# AccelCircuit_Schematic.net
KiCad netlist of a schematic drawn in EasyEDA
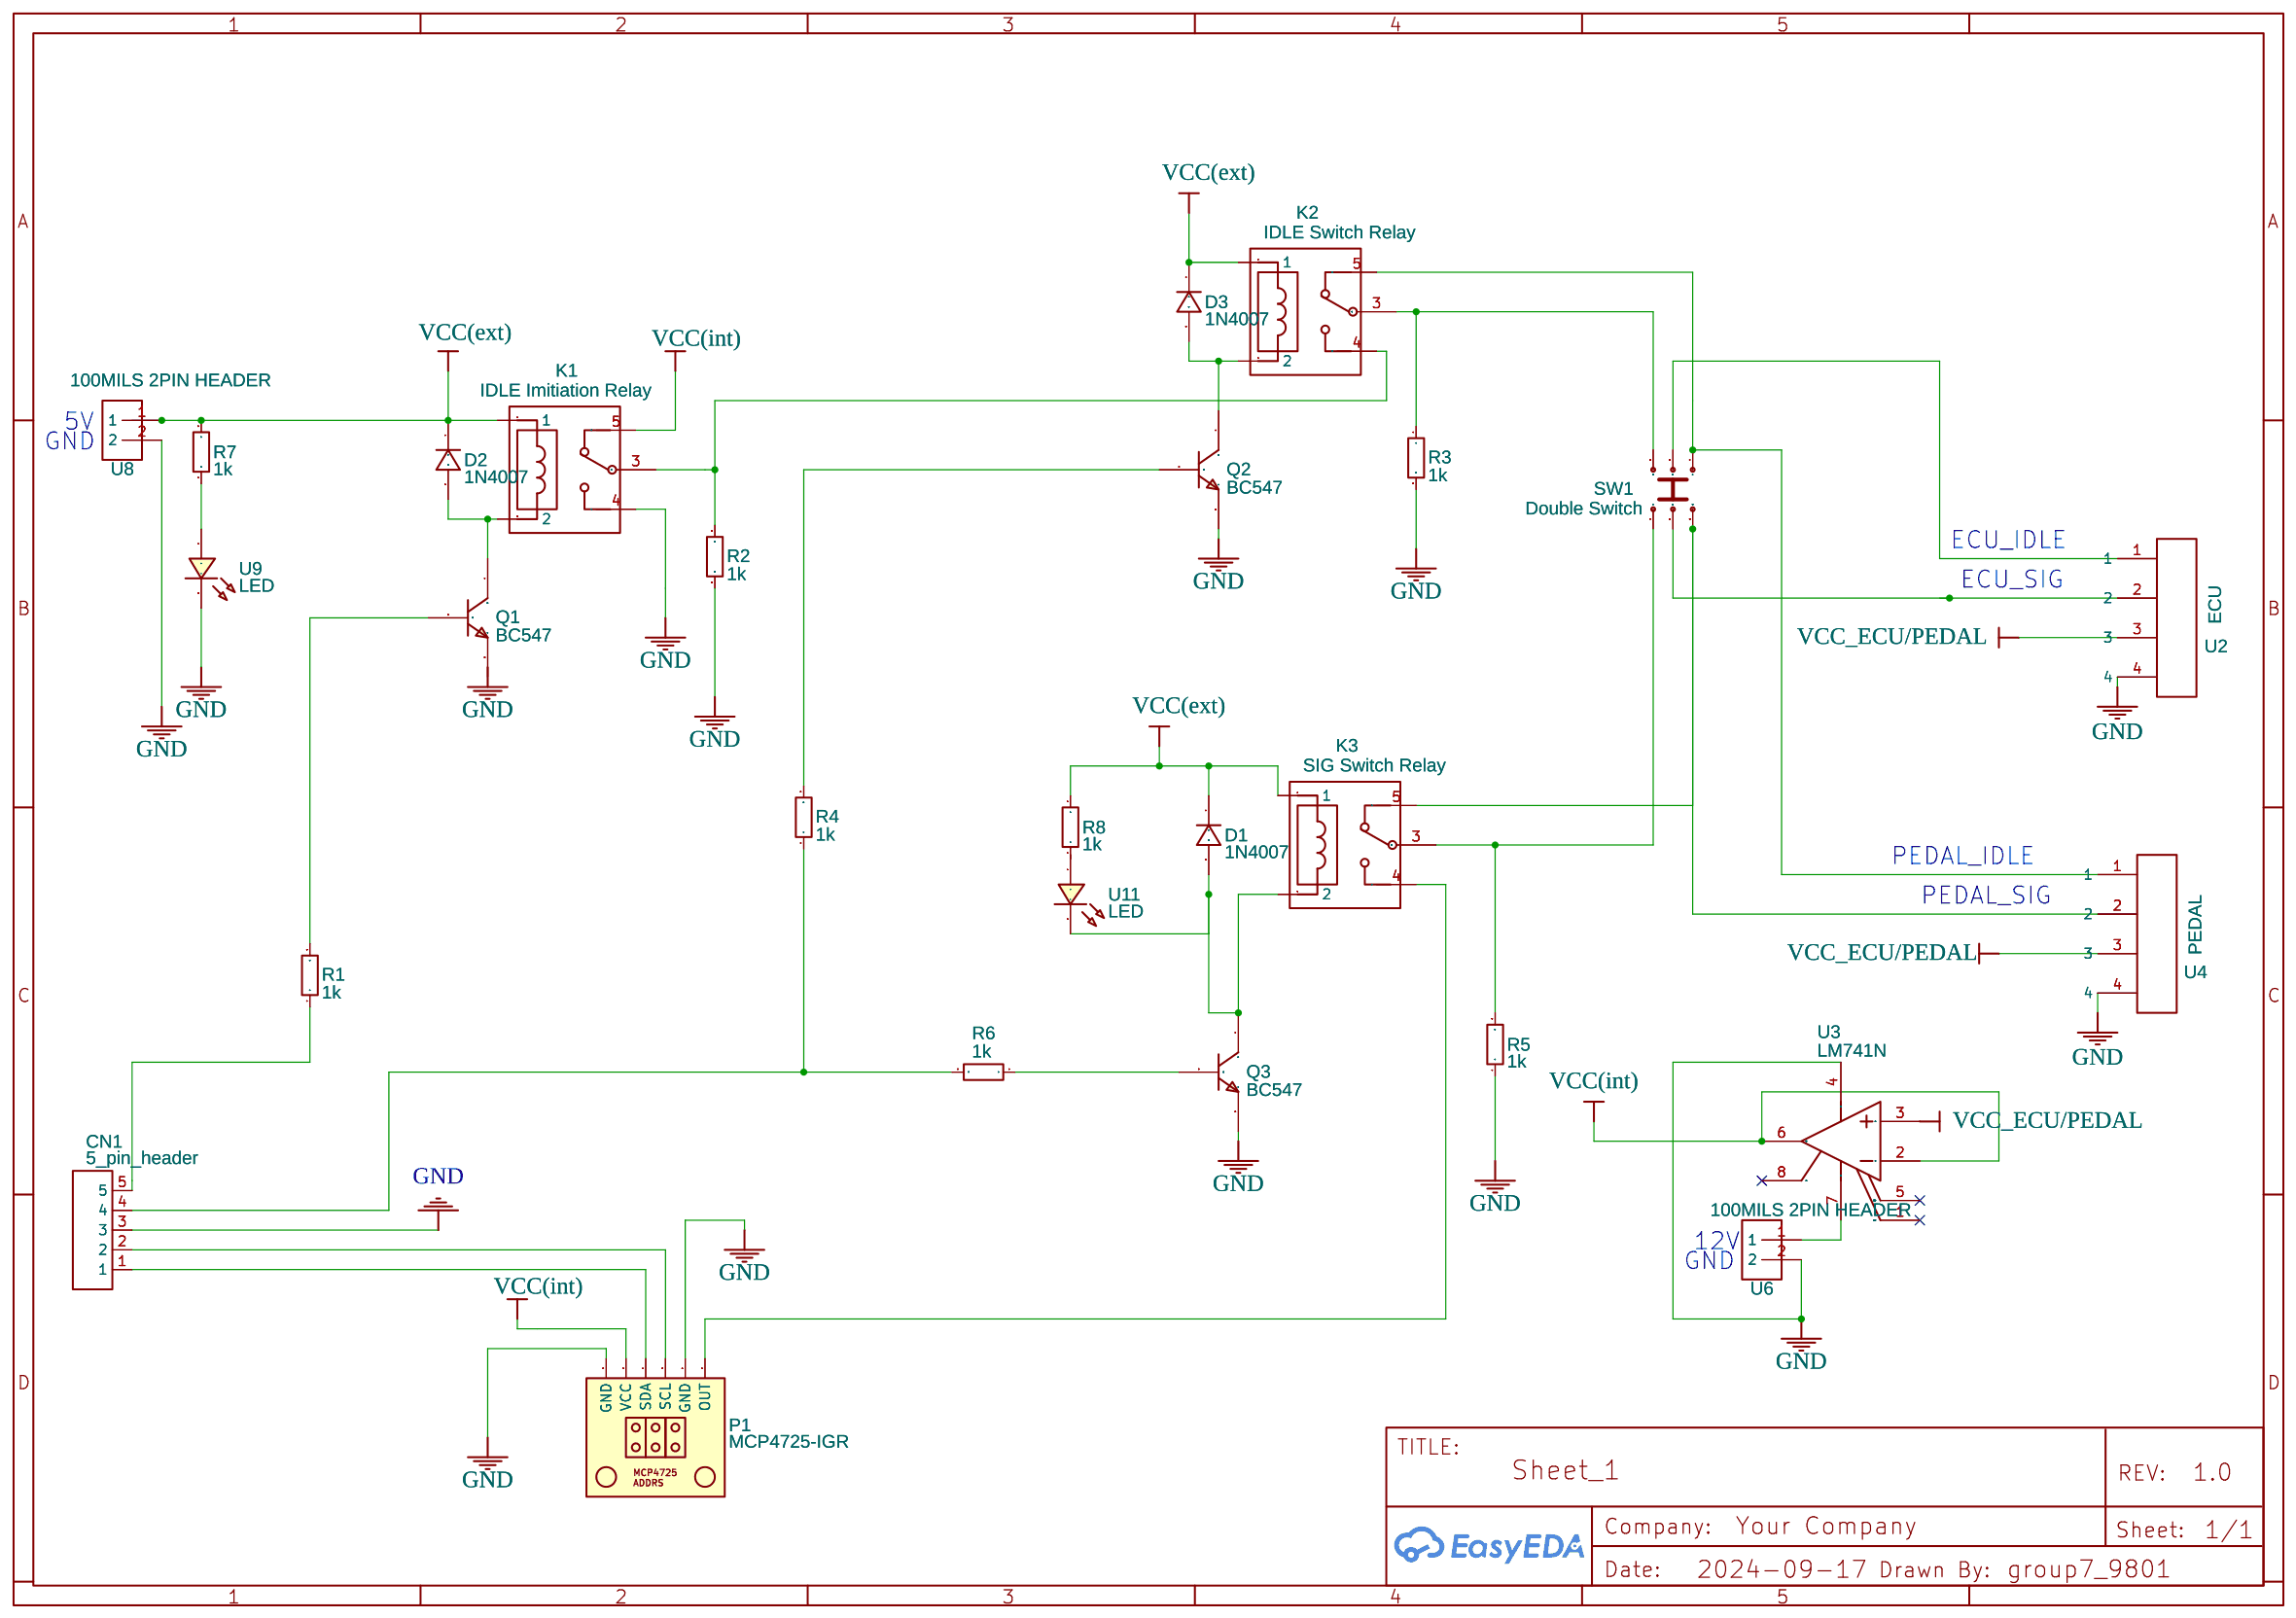
[diagram p0: schematic sheet]

(export (version "E")
  (design (tool "Eeschema 10.0.6"))
  (components
    (comp (ref "CN1")
      (value "5_pin_header")
      (fields (field (name "Manufacturer Part") "559320510") (field (name "Manufacturer") "MOLEX"))
      (libsource (lib "") (part "5_pin_header"))
    )
    (comp (ref "D1")
      (value "1N4007")
      (fields (field (name "Manufacturer") "SEMTECH"))
      (libsource (lib "") (part "1N4007"))
    )
    (comp (ref "D2")
      (value "1N4007")
      (fields (field (name "Manufacturer") "SEMTECH"))
      (libsource (lib "") (part "1N4007"))
    )
    (comp (ref "D3")
      (value "1N4007")
      (fields (field (name "Manufacturer") "SEMTECH"))
      (libsource (lib "") (part "1N4007"))
    )
    (comp (ref "K1") (value "IDLE Imitiation Relay") (libsource (lib "") (part "HRS4H-S-5V RELAY")))
    (comp (ref "K2") (value "IDLE Switch Relay") (libsource (lib "") (part "HRS4H-S-5V RELAY")))
    (comp (ref "K3") (value "SIG Switch Relay") (libsource (lib "") (part "HRS4H-S-5V RELAY")))
    (comp (ref "P1") (value "MCP4725-IGR") (libsource (lib "") (part "MCP4725-IGR")))
    (comp (ref "Q1") (value "BC547") (libsource (lib "") (part "BC547")))
    (comp (ref "Q2") (value "BC547") (libsource (lib "") (part "BC547")))
    (comp (ref "Q3") (value "BC547") (libsource (lib "") (part "BC547")))
    (comp (ref "R1")
      (value "1k")
      (fields
        (field (name "Manufacturer Part") "EWWR0001J20R0T9")
        (field (name "Manufacturer") "ResistorToday")
      )
      (libsource (lib "") (part "RESISTOR NORMAL"))
    )
    (comp (ref "R2")
      (value "1k")
      (fields
        (field (name "Manufacturer Part") "EWWR0001J20R0T9")
        (field (name "Manufacturer") "ResistorToday")
      )
      (libsource (lib "") (part "RESISTOR NORMAL_1"))
    )
    (comp (ref "R3")
      (value "1k")
      (fields
        (field (name "Manufacturer Part") "EWWR0001J20R0T9")
        (field (name "Manufacturer") "ResistorToday")
      )
      (libsource (lib "") (part "RESISTOR NORMAL_1"))
    )
    (comp (ref "R4")
      (value "1k")
      (fields
        (field (name "Manufacturer Part") "EWWR0001J20R0T9")
        (field (name "Manufacturer") "ResistorToday")
      )
      (libsource (lib "") (part "RESISTOR NORMAL"))
    )
    (comp (ref "R5")
      (value "1k")
      (fields
        (field (name "Manufacturer Part") "EWWR0001J20R0T9")
        (field (name "Manufacturer") "ResistorToday")
      )
      (libsource (lib "") (part "RESISTOR NORMAL"))
    )
    (comp (ref "R6")
      (value "1k")
      (fields
        (field (name "Manufacturer Part") "EWWR0001J20R0T9")
        (field (name "Manufacturer") "ResistorToday")
      )
      (libsource (lib "") (part "RESISTOR NORMAL_2"))
    )
    (comp (ref "R7")
      (value "1k")
      (fields
        (field (name "Manufacturer Part") "EWWR0001J20R0T9")
        (field (name "Manufacturer") "ResistorToday")
      )
      (libsource (lib "") (part "RESISTOR NORMAL"))
    )
    (comp (ref "R8")
      (value "1k")
      (fields
        (field (name "Manufacturer Part") "EWWR0001J20R0T9")
        (field (name "Manufacturer") "ResistorToday")
      )
      (libsource (lib "") (part "RESISTOR NORMAL"))
    )
    (comp (ref "SW1")
      (value "Double Switch")
      (fields
        (field (name "Manufacturer Part") "SK-12D02-VG5")
        (field (name "Manufacturer") "Rectangular Connectors - Contacts")
      )
      (libsource (lib "") (part "Double_Switch_2Pos"))
    )
    (comp (ref "U2") (value "ECU") (libsource (lib "") (part "200mils_4Pin_Header")))
    (comp (ref "U3")
      (value "LM741N")
      (fields (field (name "Manufacturer") "HGSEMI(华冠)"))
      (libsource (lib "") (part "LM741N"))
    )
    (comp (ref "U4") (value "PEDAL") (libsource (lib "") (part "200mils_4Pin_Header")))
    (comp (ref "U6") (value "100MILS 2PIN HEADER") (libsource (lib "") (part "100MILS 2PIN HEADER")))
    (comp (ref "U8") (value "100MILS 2PIN HEADER") (libsource (lib "") (part "100MILS 2PIN HEADER")))
    (comp (ref "U9")
      (value "LED")
      (fields (field (name "Manufacturer Part") "32LED-RED") (field (name "Manufacturer") "Grayhill"))
      (libsource (lib "") (part "32LED-RED"))
    )
    (comp (ref "U11")
      (value "LED")
      (fields (field (name "Manufacturer Part") "32LED-RED") (field (name "Manufacturer") "Grayhill"))
      (libsource (lib "") (part "32LED-RED"))
    )
  )
  (nets
    (net (code "1") (name "GND") (class "Default")
      (node (ref "CN1") (pin "3") (pinfunction "3_3") (pintype "unspecified"))
      (node (ref "K1") (pin "4") (pinfunction "4_4") (pintype "unspecified"))
      (node (ref "P1") (pin "2") (pinfunction "GND_2") (pintype "unspecified"))
      (node (ref "P1") (pin "6") (pinfunction "GND_6") (pintype "unspecified"))
      (node (ref "Q1") (pin "3") (pinfunction "E_3") (pintype "unspecified"))
      (node (ref "Q2") (pin "3") (pinfunction "E_3") (pintype "unspecified"))
      (node (ref "Q3") (pin "3") (pinfunction "E_3") (pintype "unspecified"))
      (node (ref "R2") (pin "2") (pinfunction "2_2") (pintype "unspecified"))
      (node (ref "R3") (pin "2") (pinfunction "2_2") (pintype "unspecified"))
      (node (ref "R5") (pin "1") (pinfunction "1_1") (pintype "unspecified"))
      (node (ref "U2") (pin "4") (pinfunction "4_4") (pintype "unspecified"))
      (node (ref "U3") (pin "4") (pinfunction "V-_4") (pintype "passive"))
      (node (ref "U4") (pin "4") (pinfunction "4_4") (pintype "unspecified"))
      (node (ref "U6") (pin "2") (pinfunction "2_2") (pintype "unspecified"))
      (node (ref "U8") (pin "2") (pinfunction "2_2") (pintype "unspecified"))
      (node (ref "U9") (pin "2") (pinfunction "-_2") (pintype "unspecified"))
    )
    (net (code "2") (name "Net-(CN1-Pad4)") (class "Default")
      (node (ref "CN1") (pin "4") (pinfunction "4_4") (pintype "unspecified"))
      (node (ref "R4") (pin "1") (pinfunction "1_1") (pintype "unspecified"))
      (node (ref "R6") (pin "2") (pinfunction "2_2") (pintype "unspecified"))
    )
    (net (code "3") (name "Net-(CN1-Pad5)") (class "Default")
      (node (ref "CN1") (pin "5") (pinfunction "5_5") (pintype "unspecified"))
      (node (ref "R1") (pin "1") (pinfunction "1_1") (pintype "unspecified"))
    )
    (net (code "4") (name "Net-(K1-Pad3)") (class "Default")
      (node (ref "K1") (pin "3") (pinfunction "3_3") (pintype "unspecified"))
      (node (ref "K2") (pin "4") (pinfunction "4_4") (pintype "unspecified"))
      (node (ref "R2") (pin "1") (pinfunction "1_1") (pintype "unspecified"))
    )
    (net (code "5") (name "Net-(K2-Pad3)") (class "Default")
      (node (ref "K2") (pin "3") (pinfunction "3_3") (pintype "unspecified"))
      (node (ref "R3") (pin "1") (pinfunction "1_1") (pintype "unspecified"))
      (node (ref "SW1") (pin "3") (pinfunction "3_3") (pintype "unspecified"))
    )
    (net (code "6") (name "Net-(K2-Pad5)") (class "Default")
      (node (ref "K2") (pin "5") (pinfunction "5_5") (pintype "unspecified"))
      (node (ref "SW1") (pin "1") (pinfunction "1_1") (pintype "unspecified"))
      (node (ref "U4") (pin "1") (pinfunction "1_1") (pintype "unspecified"))
    )
    (net (code "7") (name "Net-(K3-Pad3)") (class "Default")
      (node (ref "K3") (pin "3") (pinfunction "3_3") (pintype "unspecified"))
      (node (ref "R5") (pin "2") (pinfunction "2_2") (pintype "unspecified"))
      (node (ref "SW1") (pin "4") (pinfunction "4_4") (pintype "unspecified"))
    )
    (net (code "8") (name "Net-(K3-Pad5)") (class "Default")
      (node (ref "K3") (pin "5") (pinfunction "5_5") (pintype "unspecified"))
      (node (ref "SW1") (pin "6") (pinfunction "6_6") (pintype "unspecified"))
      (node (ref "U4") (pin "2") (pinfunction "2_2") (pintype "unspecified"))
    )
    (net (code "9") (name "Net-(P1-OUT)") (class "Default")
      (node (ref "K3") (pin "4") (pinfunction "4_4") (pintype "unspecified"))
      (node (ref "P1") (pin "1") (pinfunction "OUT_1") (pintype "unspecified"))
    )
    (net (code "10") (name "Net-(P1-SCL)") (class "Default")
      (node (ref "CN1") (pin "2") (pinfunction "2_2") (pintype "unspecified"))
      (node (ref "P1") (pin "3") (pinfunction "SCL_3") (pintype "unspecified"))
    )
    (net (code "11") (name "Net-(P1-SDA)") (class "Default")
      (node (ref "CN1") (pin "1") (pinfunction "1_1") (pintype "unspecified"))
      (node (ref "P1") (pin "4") (pinfunction "SDA_4") (pintype "unspecified"))
    )
    (net (code "12") (name "Net-(Q1-B)") (class "Default")
      (node (ref "Q1") (pin "2") (pinfunction "B_2") (pintype "unspecified"))
      (node (ref "R1") (pin "2") (pinfunction "2_2") (pintype "unspecified"))
    )
    (net (code "13") (name "Net-(Q1-C)") (class "Default")
      (node (ref "D2") (pin "2") (pinfunction "2_2") (pintype "unspecified"))
      (node (ref "K1") (pin "2") (pinfunction "2_2") (pintype "unspecified"))
      (node (ref "Q1") (pin "1") (pinfunction "C_1") (pintype "unspecified"))
    )
    (net (code "14") (name "Net-(Q2-B)") (class "Default")
      (node (ref "Q2") (pin "2") (pinfunction "B_2") (pintype "unspecified"))
      (node (ref "R4") (pin "2") (pinfunction "2_2") (pintype "unspecified"))
    )
    (net (code "15") (name "Net-(Q2-C)") (class "Default")
      (node (ref "D3") (pin "2") (pinfunction "2_2") (pintype "unspecified"))
      (node (ref "K2") (pin "2") (pinfunction "2_2") (pintype "unspecified"))
      (node (ref "Q2") (pin "1") (pinfunction "C_1") (pintype "unspecified"))
    )
    (net (code "16") (name "Net-(Q3-B)") (class "Default")
      (node (ref "Q3") (pin "2") (pinfunction "B_2") (pintype "unspecified"))
      (node (ref "R6") (pin "1") (pinfunction "1_1") (pintype "unspecified"))
    )
    (net (code "17") (name "Net-(Q3-C)") (class "Default")
      (node (ref "D1") (pin "2") (pinfunction "2_2") (pintype "unspecified"))
      (node (ref "K3") (pin "2") (pinfunction "2_2") (pintype "unspecified"))
      (node (ref "Q3") (pin "1") (pinfunction "C_1") (pintype "unspecified"))
      (node (ref "U11") (pin "2") (pinfunction "-_2") (pintype "unspecified"))
    )
    (net (code "18") (name "Net-(SW1-Pad2)") (class "Default")
      (node (ref "SW1") (pin "2") (pinfunction "2_2") (pintype "unspecified"))
      (node (ref "U2") (pin "1") (pinfunction "1_1") (pintype "unspecified"))
    )
    (net (code "19") (name "Net-(SW1-Pad5)") (class "Default")
      (node (ref "SW1") (pin "5") (pinfunction "5_5") (pintype "unspecified"))
      (node (ref "U2") (pin "2") (pinfunction "2_2") (pintype "unspecified"))
    )
    (net (code "20") (name "Net-(U3-V+)") (class "Default")
      (node (ref "U3") (pin "7") (pinfunction "V+_7") (pintype "passive"))
      (node (ref "U6") (pin "1") (pinfunction "1_1") (pintype "unspecified"))
    )
    (net (code "21") (name "Net-(U9-+)") (class "Default")
      (node (ref "R7") (pin "1") (pinfunction "1_1") (pintype "unspecified"))
      (node (ref "U9") (pin "1") (pinfunction "+_1") (pintype "unspecified"))
    )
    (net (code "22") (name "Net-(U11-+)") (class "Default")
      (node (ref "R8") (pin "1") (pinfunction "1_1") (pintype "unspecified"))
      (node (ref "U11") (pin "1") (pinfunction "+_1") (pintype "unspecified"))
    )
    (net (code "23") (name "VCC(ext)") (class "Default")
      (node (ref "D1") (pin "1") (pinfunction "1_1") (pintype "unspecified"))
      (node (ref "D2") (pin "1") (pinfunction "1_1") (pintype "unspecified"))
      (node (ref "D3") (pin "1") (pinfunction "1_1") (pintype "unspecified"))
      (node (ref "K1") (pin "1") (pinfunction "1_1") (pintype "unspecified"))
      (node (ref "K2") (pin "1") (pinfunction "1_1") (pintype "unspecified"))
      (node (ref "K3") (pin "1") (pinfunction "1_1") (pintype "unspecified"))
      (node (ref "R7") (pin "2") (pinfunction "2_2") (pintype "unspecified"))
      (node (ref "R8") (pin "2") (pinfunction "2_2") (pintype "unspecified"))
      (node (ref "U8") (pin "1") (pinfunction "1_1") (pintype "unspecified"))
    )
    (net (code "24") (name "VCC(int)") (class "Default")
      (node (ref "K1") (pin "5") (pinfunction "5_5") (pintype "unspecified"))
      (node (ref "P1") (pin "5") (pinfunction "VCC_5") (pintype "unspecified"))
      (node (ref "U3") (pin "2") (pinfunction "-IN_2") (pintype "unspecified"))
      (node (ref "U3") (pin "6") (pinfunction "OUT_6") (pintype "output"))
    )
    (net (code "25") (name "VCC_ECU{slash}PEDAL") (class "Default")
      (node (ref "U2") (pin "3") (pinfunction "3_3") (pintype "unspecified"))
      (node (ref "U3") (pin "3") (pinfunction "+IN_3") (pintype "unspecified"))
      (node (ref "U4") (pin "3") (pinfunction "3_3") (pintype "unspecified"))
    )
    (net (code "26") (name "unconnected-(U3-NC-Pad8)") (class "Default")
      (node (ref "U3") (pin "8") (pinfunction "NC_8") (pintype "unspecified+no_connect"))
    )
    (net (code "27") (name "unconnected-(U3-OFFSET_NULL-Pad1)") (class "Default")
      (node (ref "U3") (pin "1") (pinfunction "OFFSET_NULL_1") (pintype "unspecified+no_connect"))
    )
    (net (code "28") (name "unconnected-(U3-OFFSET_NULL-Pad5)") (class "Default")
      (node (ref "U3") (pin "5") (pinfunction "OFFSET_NULL_5") (pintype "unspecified+no_connect"))
    )
  )
)
